# gcgc.net
KiCad netlist of a schematic drawn in EasyEDA
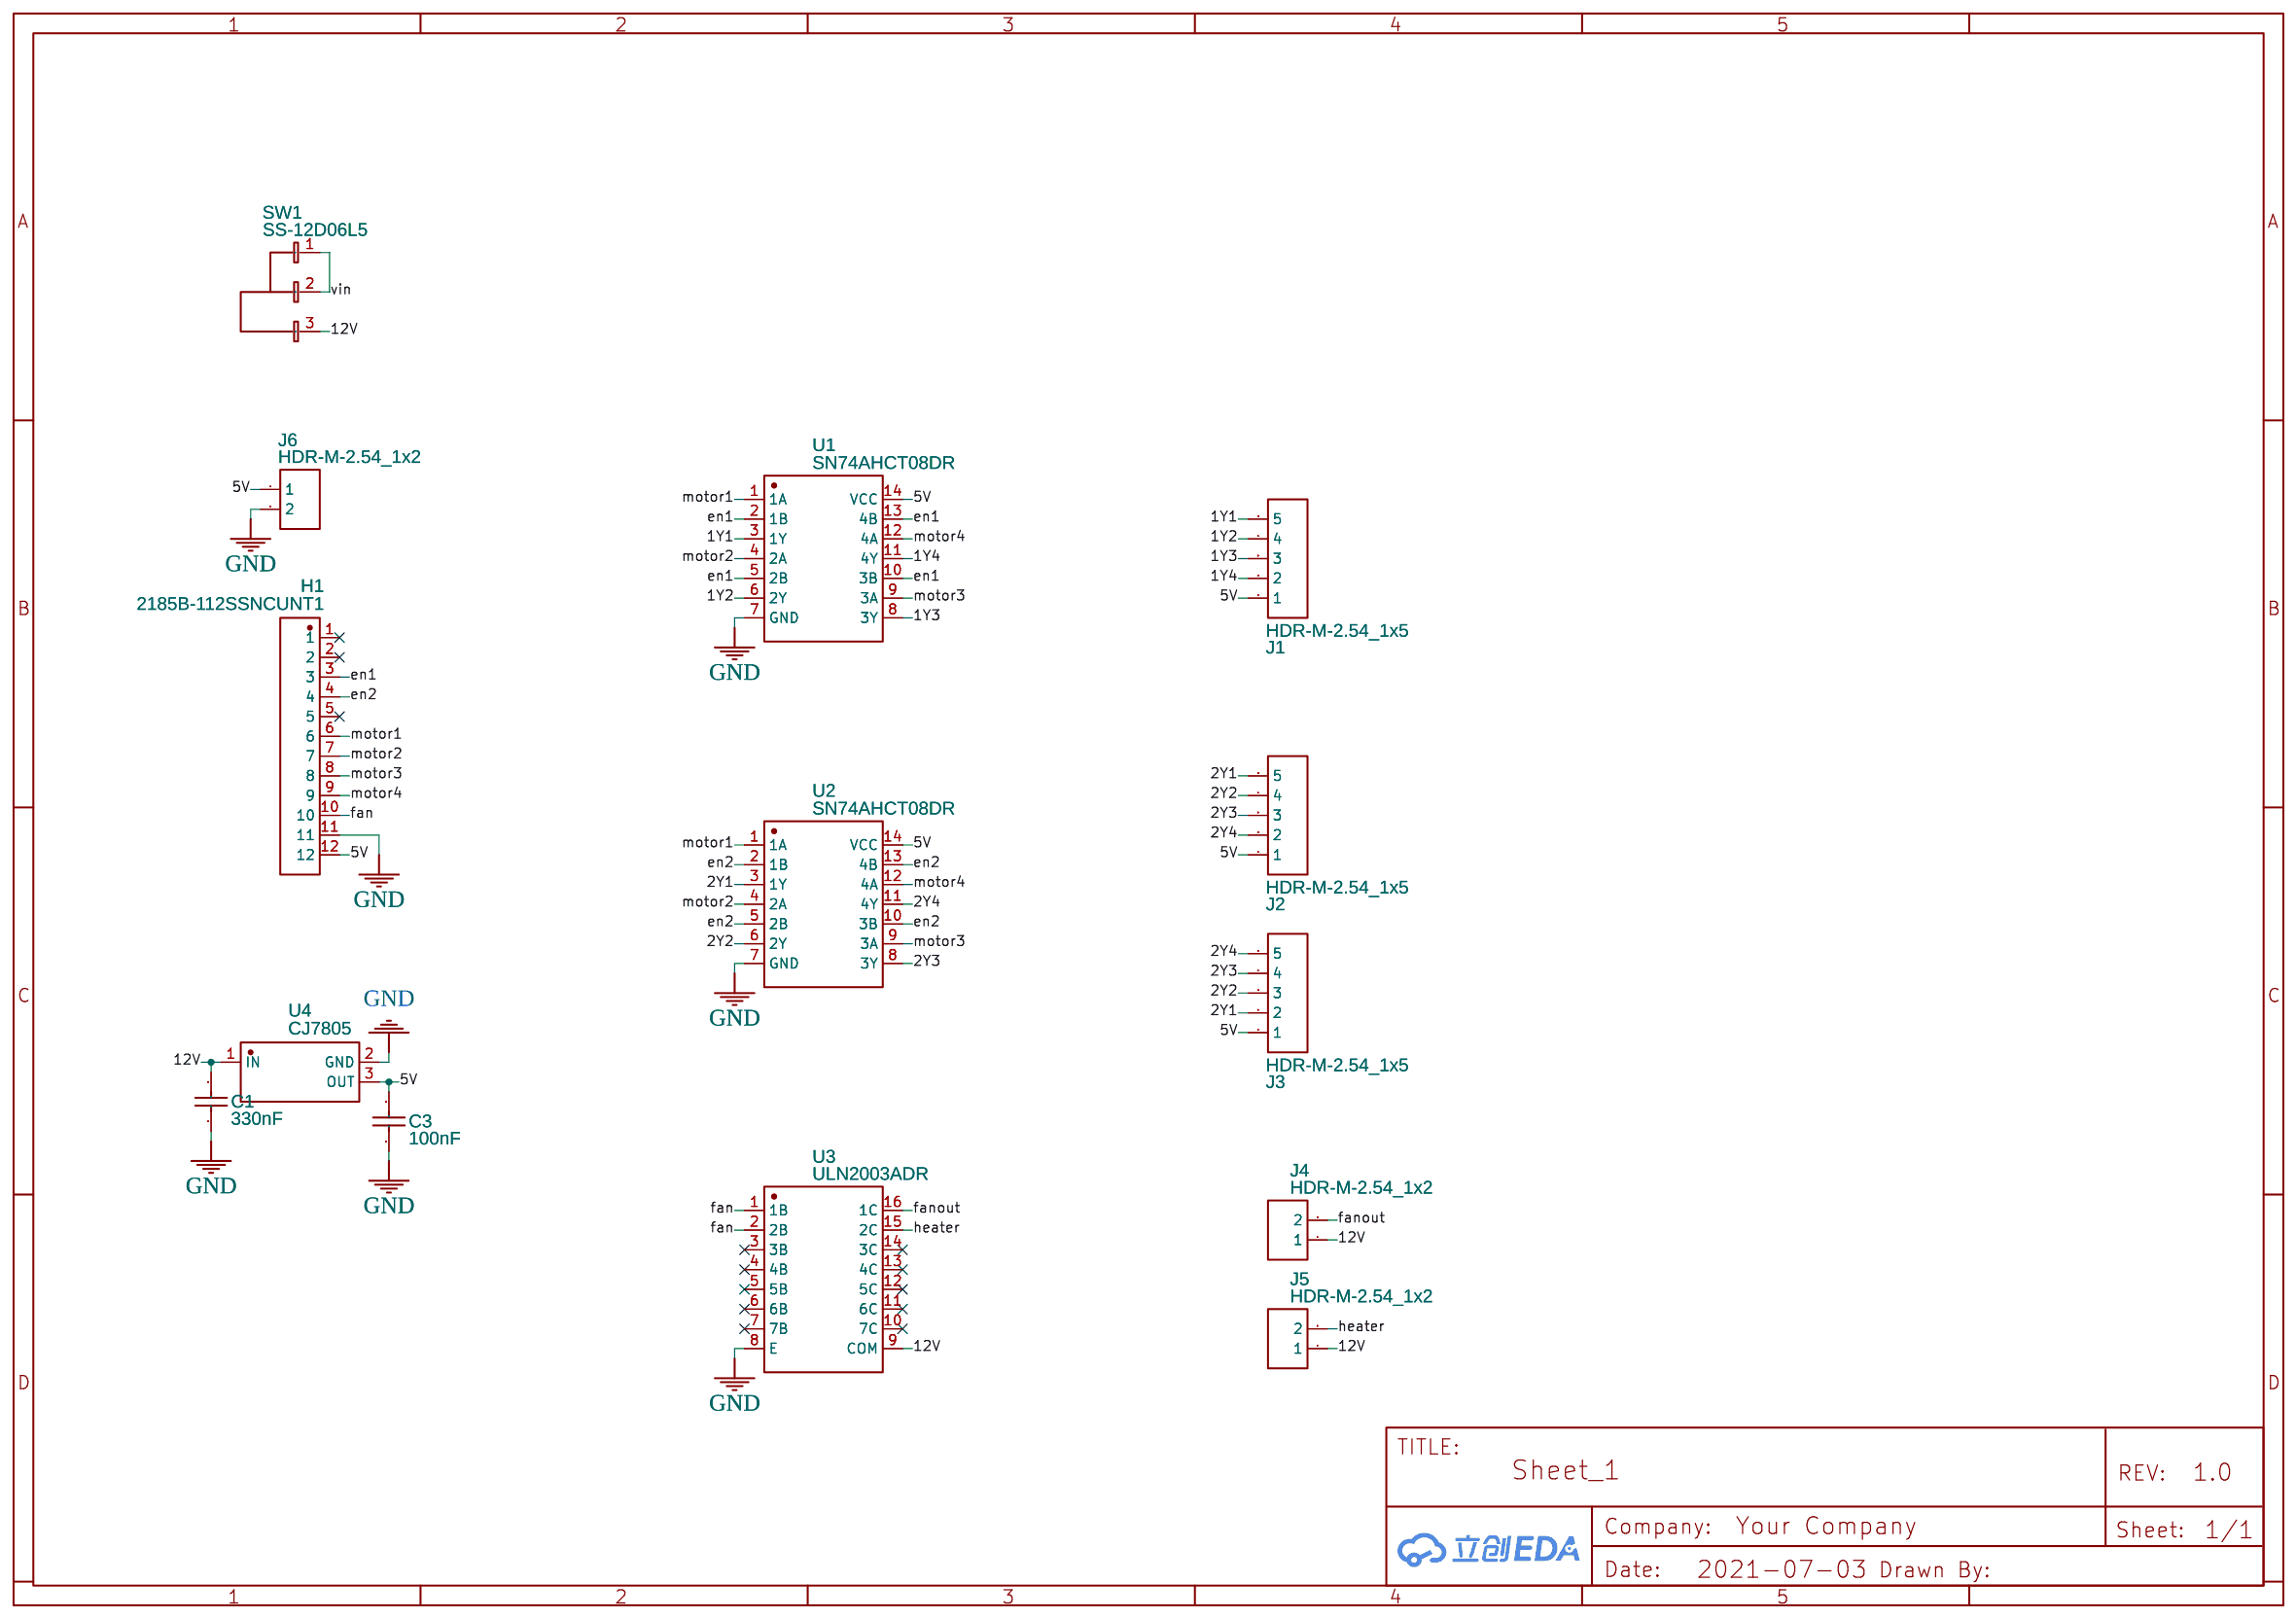
[diagram p0: schematic sheet]

(export (version "E")
  (design (tool "Eeschema 10.0.6"))
  (components
    (comp (ref "C1")
      (value "330nF")
      (fields
        (field (name "BOM_Manufacturer Part") "0805B334K500NT")
        (field (name "BOM_Supplier Part") "C1740")
      )
      (libsource (lib "") (part "0805B334K500NT"))
    )
    (comp (ref "C3")
      (value "100nF")
      (fields
        (field (name "BOM_Manufacturer Part") "CC0805KRX7R9BB104")
        (field (name "BOM_Supplier Part") "C49678")
      )
      (libsource (lib "") (part "CC0805KRX7R9BB104"))
    )
    (comp (ref "H1")
      (value "2185B-112SSNCUNT1")
      (fields (field (name "BOM_Supplier Part") "C721800"))
      (libsource (lib "") (part "2185B-112SSNCUNT1"))
    )
    (comp (ref "J1")
      (value "HDR-M-2.54_1x5")
      (fields (field (name "BOM_Supplier Part") "C358687"))
      (libsource (lib "") (part "HDR-M-2.54_1x5"))
    )
    (comp (ref "J2")
      (value "HDR-M-2.54_1x5")
      (fields (field (name "BOM_Supplier Part") "C358687"))
      (libsource (lib "") (part "HDR-M-2.54_1x5"))
    )
    (comp (ref "J3")
      (value "HDR-M-2.54_1x5")
      (fields (field (name "BOM_Supplier Part") "C358687"))
      (libsource (lib "") (part "HDR-M-2.54_1x5"))
    )
    (comp (ref "J4")
      (value "HDR-M-2.54_1x2")
      (fields (field (name "BOM_Supplier Part") "C124375"))
      (libsource (lib "") (part "HDR-M-2.54_1x2"))
    )
    (comp (ref "J5")
      (value "HDR-M-2.54_1x2")
      (fields (field (name "BOM_Supplier Part") "C124375"))
      (libsource (lib "") (part "HDR-M-2.54_1x2"))
    )
    (comp (ref "J6")
      (value "HDR-M-2.54_1x2")
      (fields (field (name "BOM_Supplier Part") "C124375"))
      (libsource (lib "") (part "HDR-M-2.54_1x2_1"))
    )
    (comp (ref "SW1")
      (value "SS-12D06L5")
      (fields (field (name "BOM_Supplier Part") "C319015"))
      (libsource (lib "") (part "SS-12D06L5"))
    )
    (comp (ref "U1")
      (value "SN74AHCT08DR")
      (fields (field (name "BOM_Supplier Part") "C7480"))
      (libsource (lib "") (part "SN74AHCT08DR"))
    )
    (comp (ref "U2")
      (value "SN74AHCT08DR")
      (fields (field (name "BOM_Supplier Part") "C7480"))
      (libsource (lib "") (part "SN74AHCT08DR"))
    )
    (comp (ref "U3")
      (value "ULN2003ADR")
      (fields (field (name "BOM_Supplier Part") "C7512"))
      (libsource (lib "") (part "ULN2003ADR"))
    )
    (comp (ref "U4")
      (value "CJ7805")
      (fields (field (name "BOM_Supplier Part") "C131137"))
      (libsource (lib "") (part "CJ7805"))
    )
  )
  (nets
    (net (code "1") (name "/1Y1") (class "Default")
      (node (ref "J1") (pin "5") (pinfunction "5_5") (pintype "unspecified"))
      (node (ref "U1") (pin "3") (pinfunction "1Y_3") (pintype "unspecified"))
    )
    (net (code "2") (name "/1Y2") (class "Default")
      (node (ref "J1") (pin "4") (pinfunction "4_4") (pintype "unspecified"))
      (node (ref "U1") (pin "6") (pinfunction "2Y_6") (pintype "unspecified"))
    )
    (net (code "3") (name "/1Y3") (class "Default")
      (node (ref "J1") (pin "3") (pinfunction "3_3") (pintype "unspecified"))
      (node (ref "U1") (pin "8") (pinfunction "3Y_8") (pintype "unspecified"))
    )
    (net (code "4") (name "/1Y4") (class "Default")
      (node (ref "J1") (pin "2") (pinfunction "2_2") (pintype "unspecified"))
      (node (ref "U1") (pin "11") (pinfunction "4Y_11") (pintype "unspecified"))
    )
    (net (code "5") (name "/2Y1") (class "Default")
      (node (ref "J2") (pin "5") (pinfunction "5_5") (pintype "unspecified"))
      (node (ref "J3") (pin "2") (pinfunction "2_2") (pintype "unspecified"))
      (node (ref "U2") (pin "3") (pinfunction "1Y_3") (pintype "unspecified"))
    )
    (net (code "6") (name "/2Y2") (class "Default")
      (node (ref "J2") (pin "4") (pinfunction "4_4") (pintype "unspecified"))
      (node (ref "J3") (pin "3") (pinfunction "3_3") (pintype "unspecified"))
      (node (ref "U2") (pin "6") (pinfunction "2Y_6") (pintype "unspecified"))
    )
    (net (code "7") (name "/2Y3") (class "Default")
      (node (ref "J2") (pin "3") (pinfunction "3_3") (pintype "unspecified"))
      (node (ref "J3") (pin "4") (pinfunction "4_4") (pintype "unspecified"))
      (node (ref "U2") (pin "8") (pinfunction "3Y_8") (pintype "unspecified"))
    )
    (net (code "8") (name "/2Y4") (class "Default")
      (node (ref "J2") (pin "2") (pinfunction "2_2") (pintype "unspecified"))
      (node (ref "J3") (pin "5") (pinfunction "5_5") (pintype "unspecified"))
      (node (ref "U2") (pin "11") (pinfunction "4Y_11") (pintype "unspecified"))
    )
    (net (code "9") (name "/5V") (class "Default")
      (node (ref "C3") (pin "1") (pinfunction "1_1") (pintype "input"))
      (node (ref "H1") (pin "12") (pinfunction "12_12") (pintype "unspecified"))
      (node (ref "J1") (pin "1") (pinfunction "1_1") (pintype "unspecified"))
      (node (ref "J2") (pin "1") (pinfunction "1_1") (pintype "unspecified"))
      (node (ref "J3") (pin "1") (pinfunction "1_1") (pintype "unspecified"))
      (node (ref "J6") (pin "1") (pinfunction "1_1") (pintype "unspecified"))
      (node (ref "U1") (pin "14") (pinfunction "VCC_14") (pintype "unspecified"))
      (node (ref "U2") (pin "14") (pinfunction "VCC_14") (pintype "unspecified"))
      (node (ref "U4") (pin "3") (pinfunction "OUT_3") (pintype "unspecified"))
    )
    (net (code "10") (name "/12V") (class "Default")
      (node (ref "C1") (pin "1") (pinfunction "1_1") (pintype "input"))
      (node (ref "J4") (pin "1") (pinfunction "1_1") (pintype "unspecified"))
      (node (ref "J5") (pin "1") (pinfunction "1_1") (pintype "unspecified"))
      (node (ref "SW1") (pin "3") (pinfunction "3_3") (pintype "unspecified"))
      (node (ref "U3") (pin "9") (pinfunction "COM_9") (pintype "unspecified"))
      (node (ref "U4") (pin "1") (pinfunction "IN_1") (pintype "unspecified"))
    )
    (net (code "11") (name "/en1") (class "Default")
      (node (ref "H1") (pin "3") (pinfunction "3_3") (pintype "unspecified"))
      (node (ref "U1") (pin "10") (pinfunction "3B_10") (pintype "unspecified"))
      (node (ref "U1") (pin "13") (pinfunction "4B_13") (pintype "unspecified"))
      (node (ref "U1") (pin "2") (pinfunction "1B_2") (pintype "unspecified"))
      (node (ref "U1") (pin "5") (pinfunction "2B_5") (pintype "unspecified"))
    )
    (net (code "12") (name "/en2") (class "Default")
      (node (ref "H1") (pin "4") (pinfunction "4_4") (pintype "unspecified"))
      (node (ref "U2") (pin "10") (pinfunction "3B_10") (pintype "unspecified"))
      (node (ref "U2") (pin "13") (pinfunction "4B_13") (pintype "unspecified"))
      (node (ref "U2") (pin "2") (pinfunction "1B_2") (pintype "unspecified"))
      (node (ref "U2") (pin "5") (pinfunction "2B_5") (pintype "unspecified"))
    )
    (net (code "13") (name "/fan") (class "Default")
      (node (ref "H1") (pin "10") (pinfunction "10_10") (pintype "unspecified"))
      (node (ref "U3") (pin "1") (pinfunction "1B_1") (pintype "unspecified"))
      (node (ref "U3") (pin "2") (pinfunction "2B_2") (pintype "unspecified"))
    )
    (net (code "14") (name "/fanout") (class "Default")
      (node (ref "J4") (pin "2") (pinfunction "2_2") (pintype "unspecified"))
      (node (ref "U3") (pin "16") (pinfunction "1C_16") (pintype "unspecified"))
    )
    (net (code "15") (name "/heater") (class "Default")
      (node (ref "J5") (pin "2") (pinfunction "2_2") (pintype "unspecified"))
      (node (ref "U3") (pin "15") (pinfunction "2C_15") (pintype "unspecified"))
    )
    (net (code "16") (name "/motor1") (class "Default")
      (node (ref "H1") (pin "6") (pinfunction "6_6") (pintype "unspecified"))
      (node (ref "U1") (pin "1") (pinfunction "1A_1") (pintype "unspecified"))
      (node (ref "U2") (pin "1") (pinfunction "1A_1") (pintype "unspecified"))
    )
    (net (code "17") (name "/motor2") (class "Default")
      (node (ref "H1") (pin "7") (pinfunction "7_7") (pintype "unspecified"))
      (node (ref "U1") (pin "4") (pinfunction "2A_4") (pintype "unspecified"))
      (node (ref "U2") (pin "4") (pinfunction "2A_4") (pintype "unspecified"))
    )
    (net (code "18") (name "/motor3") (class "Default")
      (node (ref "H1") (pin "8") (pinfunction "8_8") (pintype "unspecified"))
      (node (ref "U1") (pin "9") (pinfunction "3A_9") (pintype "unspecified"))
      (node (ref "U2") (pin "9") (pinfunction "3A_9") (pintype "unspecified"))
    )
    (net (code "19") (name "/motor4") (class "Default")
      (node (ref "H1") (pin "9") (pinfunction "9_9") (pintype "unspecified"))
      (node (ref "U1") (pin "12") (pinfunction "4A_12") (pintype "unspecified"))
      (node (ref "U2") (pin "12") (pinfunction "4A_12") (pintype "unspecified"))
    )
    (net (code "20") (name "/vin") (class "Default")
      (node (ref "SW1") (pin "1") (pinfunction "1_1") (pintype "unspecified"))
      (node (ref "SW1") (pin "2") (pinfunction "2_2") (pintype "unspecified"))
    )
    (net (code "21") (name "GND") (class "Default")
      (node (ref "C1") (pin "2") (pinfunction "2_2") (pintype "input"))
      (node (ref "C3") (pin "2") (pinfunction "2_2") (pintype "input"))
      (node (ref "H1") (pin "11") (pinfunction "11_11") (pintype "unspecified"))
      (node (ref "J6") (pin "2") (pinfunction "2_2") (pintype "unspecified"))
      (node (ref "U1") (pin "7") (pinfunction "GND_7") (pintype "unspecified"))
      (node (ref "U2") (pin "7") (pinfunction "GND_7") (pintype "unspecified"))
      (node (ref "U3") (pin "8") (pinfunction "E_8") (pintype "unspecified"))
      (node (ref "U4") (pin "2") (pinfunction "GND_2") (pintype "unspecified"))
    )
    (net (code "22") (name "unconnected-(H1-Pad1)") (class "Default")
      (node (ref "H1") (pin "1") (pinfunction "1_1") (pintype "unspecified+no_connect"))
    )
    (net (code "23") (name "unconnected-(H1-Pad2)") (class "Default")
      (node (ref "H1") (pin "2") (pinfunction "2_2") (pintype "unspecified+no_connect"))
    )
    (net (code "24") (name "unconnected-(H1-Pad5)") (class "Default")
      (node (ref "H1") (pin "5") (pinfunction "5_5") (pintype "unspecified+no_connect"))
    )
    (net (code "25") (name "unconnected-(U3-3B-Pad3)") (class "Default")
      (node (ref "U3") (pin "3") (pinfunction "3B_3") (pintype "unspecified+no_connect"))
    )
    (net (code "26") (name "unconnected-(U3-3C-Pad14)") (class "Default")
      (node (ref "U3") (pin "14") (pinfunction "3C_14") (pintype "unspecified+no_connect"))
    )
    (net (code "27") (name "unconnected-(U3-4B-Pad4)") (class "Default")
      (node (ref "U3") (pin "4") (pinfunction "4B_4") (pintype "unspecified+no_connect"))
    )
    (net (code "28") (name "unconnected-(U3-4C-Pad13)") (class "Default")
      (node (ref "U3") (pin "13") (pinfunction "4C_13") (pintype "unspecified+no_connect"))
    )
    (net (code "29") (name "unconnected-(U3-5B-Pad5)") (class "Default")
      (node (ref "U3") (pin "5") (pinfunction "5B_5") (pintype "unspecified+no_connect"))
    )
    (net (code "30") (name "unconnected-(U3-5C-Pad12)") (class "Default")
      (node (ref "U3") (pin "12") (pinfunction "5C_12") (pintype "unspecified+no_connect"))
    )
    (net (code "31") (name "unconnected-(U3-6B-Pad6)") (class "Default")
      (node (ref "U3") (pin "6") (pinfunction "6B_6") (pintype "unspecified+no_connect"))
    )
    (net (code "32") (name "unconnected-(U3-6C-Pad11)") (class "Default")
      (node (ref "U3") (pin "11") (pinfunction "6C_11") (pintype "unspecified+no_connect"))
    )
    (net (code "33") (name "unconnected-(U3-7B-Pad7)") (class "Default")
      (node (ref "U3") (pin "7") (pinfunction "7B_7") (pintype "unspecified+no_connect"))
    )
    (net (code "34") (name "unconnected-(U3-7C-Pad10)") (class "Default")
      (node (ref "U3") (pin "10") (pinfunction "7C_10") (pintype "unspecified+no_connect"))
    )
  )
)
